# tm4c123_dev_board.net
KiCad netlist of a schematic drawn in Altium Designer
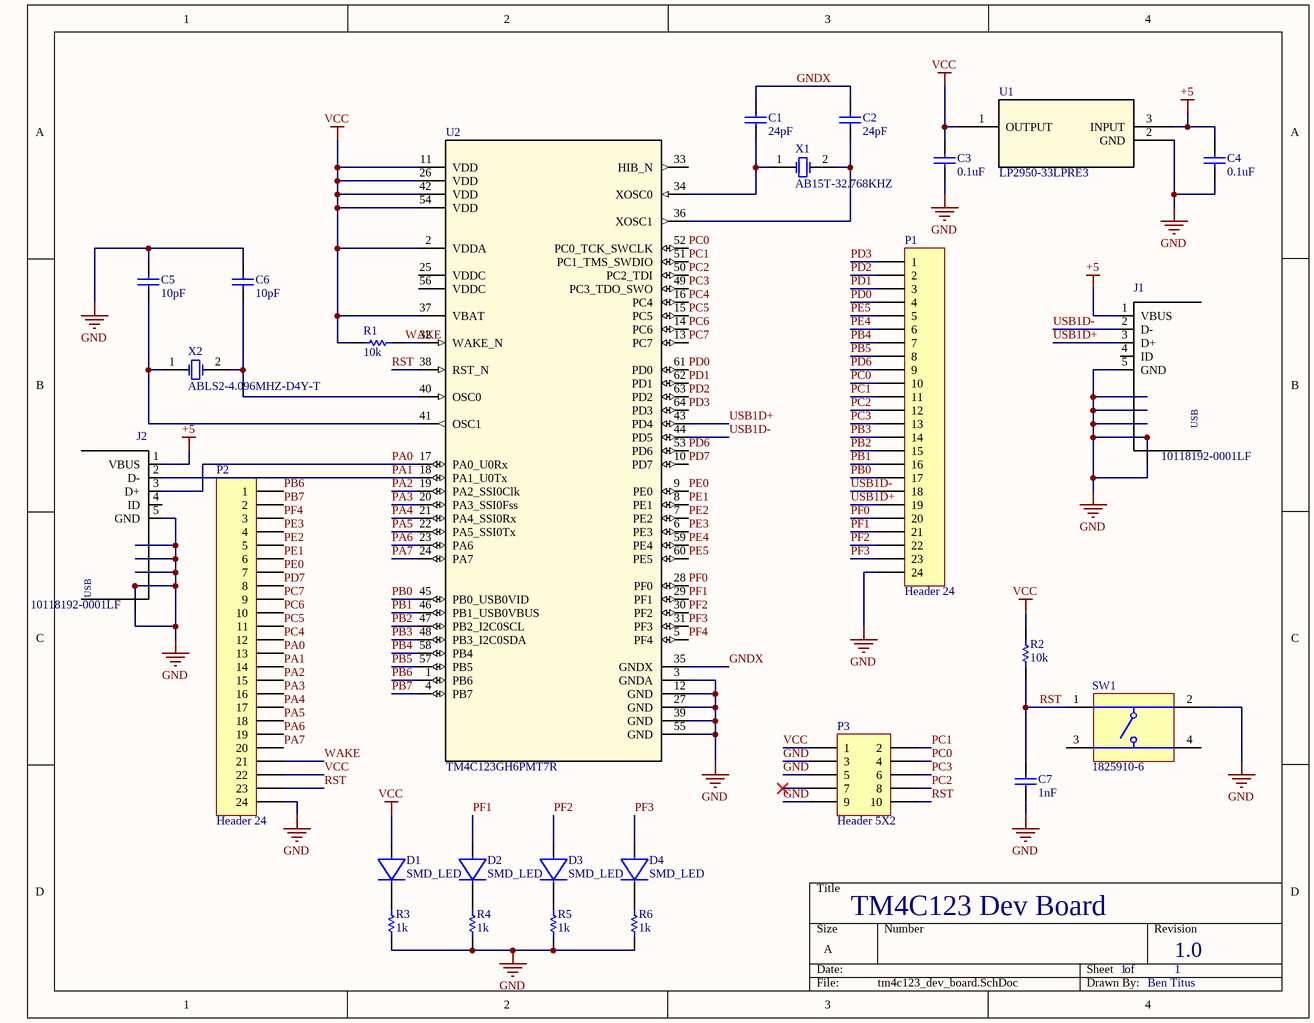
[diagram p0: tm4c123_dev_board.SchDoc]

(export (version "E")
  (design (tool "Eeschema 10.0.6"))
  (components
    (comp (ref "C1")
      (value "24pF")
      (footprint "CAPC0805(2012)145_L")
      (description "0805 (2012 Metric) Chip Capacitor")
      (libsource (lib "Altium Content Vault") (part "CAP_5"))
    )
    (comp (ref "C2")
      (value "24pF")
      (footprint "CAPC0805(2012)145_L")
      (description "0805 (2012 Metric) Chip Capacitor")
      (libsource (lib "Altium Content Vault") (part "CAP_5"))
    )
    (comp (ref "C3")
      (value "0.1uF")
      (footprint "CAPC0805(2012)145_L")
      (description "0805 (2012 Metric) Chip Capacitor")
      (libsource (lib "Altium Content Vault") (part "CAP_5"))
    )
    (comp (ref "C4")
      (value "0.1uF")
      (footprint "CAPC0805(2012)145_L")
      (description "0805 (2012 Metric) Chip Capacitor")
      (libsource (lib "Altium Content Vault") (part "CAP_5"))
    )
    (comp (ref "C5")
      (value "10pF")
      (footprint "CAPC0805(2012)145_L")
      (description "0805 (2012 Metric) Chip Capacitor")
      (libsource (lib "Altium Content Vault") (part "CAP_5"))
    )
    (comp (ref "C6")
      (value "10pF")
      (footprint "CAPC0805(2012)145_L")
      (description "0805 (2012 Metric) Chip Capacitor")
      (libsource (lib "Altium Content Vault") (part "CAP_5"))
    )
    (comp (ref "C7")
      (value "1nF")
      (footprint "CAPC0805(2012)145_L")
      (description "0805 (2012 Metric) Chip Capacitor")
      (libsource (lib "Altium Content Vault") (part "CAP_5"))
    )
    (comp (ref "D1")
      (value "SMD_LED")
      (footprint "0805 Diode")
      (libsource (lib "Custom_Lib") (part "SMD_LED"))
    )
    (comp (ref "D2")
      (value "SMD_LED")
      (footprint "0805 Diode")
      (libsource (lib "Custom_Lib") (part "SMD_LED"))
    )
    (comp (ref "D3")
      (value "SMD_LED")
      (footprint "0805 Diode")
      (libsource (lib "Custom_Lib") (part "SMD_LED"))
    )
    (comp (ref "D4")
      (value "SMD_LED")
      (footprint "0805 Diode")
      (libsource (lib "Custom_Lib") (part "SMD_LED"))
    )
    (comp (ref "J1")
      (value "10118192-0001LF")
      (footprint "10118192-0001LF_10118192-0001LF(Primary)")
      (description "CONN USB MICRO B RECPT SMT R/A")
      (fields (field (name "MF") "Amphenol"))
      (libsource (lib "Custom_Lib") (part "10118192-0001LF"))
    )
    (comp (ref "J2")
      (value "10118192-0001LF")
      (footprint "10118192-0001LF_10118192-0001LF(Primary)")
      (description "CONN USB MICRO B RECPT SMT R/A")
      (fields (field (name "MF") "Amphenol"))
      (libsource (lib "Custom_Lib") (part "10118192-0001LF"))
    )
    (comp (ref "P1")
      (value "Header 24")
      (footprint "HDR1X24")
      (description "Header, 24-Pin")
      (fields (field (name "PUBLISHER") "Altium Limited"))
      (libsource (lib "Miscellaneous Connectors") (part "Header 24"))
    )
    (comp (ref "P2")
      (value "Header 24")
      (footprint "HDR1X24")
      (description "Header, 24-Pin")
      (fields (field (name "PUBLISHER") "Altium Limited"))
      (libsource (lib "") (part "Header 24_1"))
    )
    (comp (ref "P3")
      (value "Header 5X2")
      (footprint "HDR2X5")
      (description "Header, 5-Pin, Dual row")
      (fields (field (name "PUBLISHER") "Altium Limited"))
      (libsource (lib "Miscellaneous Connectors") (part "Header 5X2"))
    )
    (comp (ref "R1")
      (value "10k")
      (footprint "RESC0805(2012)_L")
      (description "0805 (2012 Metric) Chip Resistor")
      (libsource (lib "Altium Content Vault") (part "RES_3"))
    )
    (comp (ref "R2")
      (value "10k")
      (footprint "RESC0805(2012)_L")
      (description "0805 (2012 Metric) Chip Resistor")
      (libsource (lib "Altium Content Vault") (part "RES_3"))
    )
    (comp (ref "R3")
      (value "1k")
      (footprint "RESC0805(2012)_L")
      (description "0805 (2012 Metric) Chip Resistor")
      (libsource (lib "Altium Content Vault") (part "RES_3"))
    )
    (comp (ref "R4")
      (value "1k")
      (footprint "RESC0805(2012)_L")
      (description "0805 (2012 Metric) Chip Resistor")
      (libsource (lib "Altium Content Vault") (part "RES_3"))
    )
    (comp (ref "R5")
      (value "1k")
      (footprint "RESC0805(2012)_L")
      (description "0805 (2012 Metric) Chip Resistor")
      (libsource (lib "Altium Content Vault") (part "RES_3"))
    )
    (comp (ref "R6")
      (value "1k")
      (footprint "RESC0805(2012)_L")
      (description "0805 (2012 Metric) Chip Resistor")
      (libsource (lib "Altium Content Vault") (part "RES_3"))
    )
    (comp (ref "SW1")
      (value "1825910-6")
      (footprint "TECO-1825910-6_V")
      (description "Tact Switch, SPST-NO, 0.05 A, -35 to 85 degC, 4-Pin THD, RoHS, Bulk")
      (fields (field (name "MANUFACTURER") "TE Connectivity"))
      (libsource (lib "Altium Content Vault") (part "SW-SPST-4_A"))
    )
    (comp (ref "U1")
      (value "LP2950-33LPRE3")
      (footprint "LP3")
      (description "Imported")
      (fields (field (name "MANUFACTURER") "Texas Instruments"))
      (libsource (lib "lp2950-33") (part "LP2950-33LPRE3"))
    )
    (comp (ref "U2")
      (value "TM4C123GH6PMT7R")
      (footprint "PM0064A_N")
      (description "Imported")
      (fields
        (field (name "PARTNUMBER") "TM4C123GH6PMTR")
        (field (name "ALTERNATE_PARTNUMBER") "TM4C123GH6PMT")
      )
      (libsource (lib "Custom_Lib") (part "TM4C123GH6PMT7R"))
    )
    (comp (ref "X1")
      (value "AB15T-32.768KHZ")
      (footprint "ABRA-AB15T-2_V")
      (fields (field (name "MANUFACTURER") "Abracon"))
      (libsource (lib "Altium Content Vault") (part "ABRA-XTAL_1-2-2"))
    )
    (comp (ref "X2")
      (value "ABLS2-4.096MHZ-D4Y-T")
      (footprint "ABRA-ABLS2-2_V")
      (fields (field (name "MANUFACTURER") "Abracon"))
      (libsource (lib "Altium Content Vault") (part "ABRA-XTAL_1-2-2"))
    )
  )
  (nets
    (net (code "1") (name "+5") (class "Default")
      (node (ref "C4") (pin "2") (pinfunction "2_2") (pintype "passive"))
      (node (ref "J1") (pin "1") (pinfunction "VBUS_1") (pintype "passive"))
      (node (ref "J2") (pin "1") (pinfunction "VBUS_1") (pintype "passive"))
      (node (ref "U1") (pin "3") (pinfunction "INPUT_3") (pintype "power_in"))
    )
    (net (code "2") (name "/GNDX") (class "Default")
      (node (ref "C1") (pin "2") (pinfunction "2_2") (pintype "passive"))
      (node (ref "C2") (pin "2") (pinfunction "2_2") (pintype "passive"))
      (node (ref "U2") (pin "35") (pinfunction "GNDX_35") (pintype "power_in"))
    )
    (net (code "3") (name "/PA0") (class "Default")
      (node (ref "J2") (pin "3") (pinfunction "D+_3") (pintype "passive"))
      (node (ref "P2") (pin "13") (pinfunction "13_13") (pintype "passive"))
      (node (ref "U2") (pin "17") (pinfunction "PA0_U0Rx_17") (pintype "bidirectional"))
    )
    (net (code "4") (name "/PA1") (class "Default")
      (node (ref "J2") (pin "2") (pinfunction "D-_2") (pintype "passive"))
      (node (ref "P2") (pin "14") (pinfunction "14_14") (pintype "passive"))
      (node (ref "U2") (pin "18") (pinfunction "PA1_U0Tx_18") (pintype "bidirectional"))
    )
    (net (code "5") (name "/PA2") (class "Default")
      (node (ref "P2") (pin "15") (pinfunction "15_15") (pintype "passive"))
      (node (ref "U2") (pin "19") (pinfunction "PA2_SSI0Clk_19") (pintype "bidirectional"))
    )
    (net (code "6") (name "/PA3") (class "Default")
      (node (ref "P2") (pin "16") (pinfunction "16_16") (pintype "passive"))
      (node (ref "U2") (pin "20") (pinfunction "PA3_SSI0Fss_20") (pintype "bidirectional"))
    )
    (net (code "7") (name "/PA4") (class "Default")
      (node (ref "P2") (pin "17") (pinfunction "17_17") (pintype "passive"))
      (node (ref "U2") (pin "21") (pinfunction "PA4_SSI0Rx_21") (pintype "bidirectional"))
    )
    (net (code "8") (name "/PA5") (class "Default")
      (node (ref "P2") (pin "18") (pinfunction "18_18") (pintype "passive"))
      (node (ref "U2") (pin "22") (pinfunction "PA5_SSI0Tx_22") (pintype "bidirectional"))
    )
    (net (code "9") (name "/PA6") (class "Default")
      (node (ref "P2") (pin "19") (pinfunction "19_19") (pintype "passive"))
      (node (ref "U2") (pin "23") (pinfunction "PA6_23") (pintype "bidirectional"))
    )
    (net (code "10") (name "/PA7") (class "Default")
      (node (ref "P2") (pin "20") (pinfunction "20_20") (pintype "passive"))
      (node (ref "U2") (pin "24") (pinfunction "PA7_24") (pintype "bidirectional"))
    )
    (net (code "11") (name "/PB0") (class "Default")
      (node (ref "P1") (pin "17") (pinfunction "17_17") (pintype "passive"))
      (node (ref "U2") (pin "45") (pinfunction "PB0_USB0VID_45") (pintype "bidirectional"))
    )
    (net (code "12") (name "/PB1") (class "Default")
      (node (ref "P1") (pin "16") (pinfunction "16_16") (pintype "passive"))
      (node (ref "U2") (pin "46") (pinfunction "PB1_USB0VBUS_46") (pintype "bidirectional"))
    )
    (net (code "13") (name "/PB2") (class "Default")
      (node (ref "P1") (pin "15") (pinfunction "15_15") (pintype "passive"))
      (node (ref "U2") (pin "47") (pinfunction "PB2_I2C0SCL_47") (pintype "bidirectional"))
    )
    (net (code "14") (name "/PB3") (class "Default")
      (node (ref "P1") (pin "14") (pinfunction "14_14") (pintype "passive"))
      (node (ref "U2") (pin "48") (pinfunction "PB3_I2C0SDA_48") (pintype "bidirectional"))
    )
    (net (code "15") (name "/PB4") (class "Default")
      (node (ref "P1") (pin "7") (pinfunction "7_7") (pintype "passive"))
      (node (ref "U2") (pin "58") (pinfunction "PB4_58") (pintype "bidirectional"))
    )
    (net (code "16") (name "/PB5") (class "Default")
      (node (ref "P1") (pin "8") (pinfunction "8_8") (pintype "passive"))
      (node (ref "U2") (pin "57") (pinfunction "PB5_57") (pintype "bidirectional"))
    )
    (net (code "17") (name "/PB6") (class "Default")
      (node (ref "P2") (pin "1") (pinfunction "1_1") (pintype "passive"))
      (node (ref "U2") (pin "1") (pinfunction "PB6_1") (pintype "bidirectional"))
    )
    (net (code "18") (name "/PB7") (class "Default")
      (node (ref "P2") (pin "2") (pinfunction "2_2") (pintype "passive"))
      (node (ref "U2") (pin "4") (pinfunction "PB7_4") (pintype "bidirectional"))
    )
    (net (code "19") (name "/PC0") (class "Default")
      (node (ref "P1") (pin "10") (pinfunction "10_10") (pintype "passive"))
      (node (ref "P3") (pin "4") (pinfunction "4_4") (pintype "passive"))
      (node (ref "U2") (pin "52") (pinfunction "PC0_TCK_SWCLK_52") (pintype "bidirectional"))
    )
    (net (code "20") (name "/PC1") (class "Default")
      (node (ref "P1") (pin "11") (pinfunction "11_11") (pintype "passive"))
      (node (ref "P3") (pin "2") (pinfunction "2_2") (pintype "passive"))
      (node (ref "U2") (pin "51") (pinfunction "PC1_TMS_SWDIO_51") (pintype "bidirectional"))
    )
    (net (code "21") (name "/PC2") (class "Default")
      (node (ref "P1") (pin "12") (pinfunction "12_12") (pintype "passive"))
      (node (ref "P3") (pin "8") (pinfunction "8_8") (pintype "passive"))
      (node (ref "U2") (pin "50") (pinfunction "PC2_TDI_50") (pintype "bidirectional"))
    )
    (net (code "22") (name "/PC3") (class "Default")
      (node (ref "P1") (pin "13") (pinfunction "13_13") (pintype "passive"))
      (node (ref "P3") (pin "6") (pinfunction "6_6") (pintype "passive"))
      (node (ref "U2") (pin "49") (pinfunction "PC3_TDO_SWO_49") (pintype "bidirectional"))
    )
    (net (code "23") (name "/PC4") (class "Default")
      (node (ref "P2") (pin "12") (pinfunction "12_12") (pintype "passive"))
      (node (ref "U2") (pin "16") (pinfunction "PC4_16") (pintype "bidirectional"))
    )
    (net (code "24") (name "/PC5") (class "Default")
      (node (ref "P2") (pin "11") (pinfunction "11_11") (pintype "passive"))
      (node (ref "U2") (pin "15") (pinfunction "PC5_15") (pintype "bidirectional"))
    )
    (net (code "25") (name "/PC6") (class "Default")
      (node (ref "P2") (pin "10") (pinfunction "10_10") (pintype "passive"))
      (node (ref "U2") (pin "14") (pinfunction "PC6_14") (pintype "bidirectional"))
    )
    (net (code "26") (name "/PC7") (class "Default")
      (node (ref "P2") (pin "9") (pinfunction "9_9") (pintype "passive"))
      (node (ref "U2") (pin "13") (pinfunction "PC7_13") (pintype "bidirectional"))
    )
    (net (code "27") (name "/PD0") (class "Default")
      (node (ref "P1") (pin "4") (pinfunction "4_4") (pintype "passive"))
      (node (ref "U2") (pin "61") (pinfunction "PD0_61") (pintype "bidirectional"))
    )
    (net (code "28") (name "/PD1") (class "Default")
      (node (ref "P1") (pin "3") (pinfunction "3_3") (pintype "passive"))
      (node (ref "U2") (pin "62") (pinfunction "PD1_62") (pintype "bidirectional"))
    )
    (net (code "29") (name "/PD2") (class "Default")
      (node (ref "P1") (pin "2") (pinfunction "2_2") (pintype "passive"))
      (node (ref "U2") (pin "63") (pinfunction "PD2_63") (pintype "bidirectional"))
    )
    (net (code "30") (name "/PD3") (class "Default")
      (node (ref "P1") (pin "1") (pinfunction "1_1") (pintype "passive"))
      (node (ref "U2") (pin "64") (pinfunction "PD3_64") (pintype "bidirectional"))
    )
    (net (code "31") (name "/PD6") (class "Default")
      (node (ref "P1") (pin "9") (pinfunction "9_9") (pintype "passive"))
      (node (ref "U2") (pin "53") (pinfunction "PD6_53") (pintype "bidirectional"))
    )
    (net (code "32") (name "/PD7") (class "Default")
      (node (ref "P2") (pin "8") (pinfunction "8_8") (pintype "passive"))
      (node (ref "U2") (pin "10") (pinfunction "PD7_10") (pintype "bidirectional"))
    )
    (net (code "33") (name "/PE0") (class "Default")
      (node (ref "P2") (pin "7") (pinfunction "7_7") (pintype "passive"))
      (node (ref "U2") (pin "9") (pinfunction "PE0_9") (pintype "bidirectional"))
    )
    (net (code "34") (name "/PE1") (class "Default")
      (node (ref "P2") (pin "6") (pinfunction "6_6") (pintype "passive"))
      (node (ref "U2") (pin "8") (pinfunction "PE1_8") (pintype "bidirectional"))
    )
    (net (code "35") (name "/PE2") (class "Default")
      (node (ref "P2") (pin "5") (pinfunction "5_5") (pintype "passive"))
      (node (ref "U2") (pin "7") (pinfunction "PE2_7") (pintype "bidirectional"))
    )
    (net (code "36") (name "/PE3") (class "Default")
      (node (ref "P2") (pin "4") (pinfunction "4_4") (pintype "passive"))
      (node (ref "U2") (pin "6") (pinfunction "PE3_6") (pintype "bidirectional"))
    )
    (net (code "37") (name "/PE4") (class "Default")
      (node (ref "P1") (pin "6") (pinfunction "6_6") (pintype "passive"))
      (node (ref "U2") (pin "59") (pinfunction "PE4_59") (pintype "bidirectional"))
    )
    (net (code "38") (name "/PE5") (class "Default")
      (node (ref "P1") (pin "5") (pinfunction "5_5") (pintype "passive"))
      (node (ref "U2") (pin "60") (pinfunction "PE5_60") (pintype "bidirectional"))
    )
    (net (code "39") (name "/PF0") (class "Default")
      (node (ref "P1") (pin "20") (pinfunction "20_20") (pintype "passive"))
      (node (ref "U2") (pin "28") (pinfunction "PF0_28") (pintype "bidirectional"))
    )
    (net (code "40") (name "/PF1") (class "Default")
      (node (ref "D2") (pin "1") (pintype "passive"))
      (node (ref "P1") (pin "21") (pinfunction "21_21") (pintype "passive"))
      (node (ref "U2") (pin "29") (pinfunction "PF1_29") (pintype "bidirectional"))
    )
    (net (code "41") (name "/PF2") (class "Default")
      (node (ref "D3") (pin "1") (pintype "passive"))
      (node (ref "P1") (pin "22") (pinfunction "22_22") (pintype "passive"))
      (node (ref "U2") (pin "30") (pinfunction "PF2_30") (pintype "bidirectional"))
    )
    (net (code "42") (name "/PF3") (class "Default")
      (node (ref "D4") (pin "1") (pintype "passive"))
      (node (ref "P1") (pin "23") (pinfunction "23_23") (pintype "passive"))
      (node (ref "U2") (pin "31") (pinfunction "PF3_31") (pintype "bidirectional"))
    )
    (net (code "43") (name "/PF4") (class "Default")
      (node (ref "P2") (pin "3") (pinfunction "3_3") (pintype "passive"))
      (node (ref "U2") (pin "5") (pinfunction "PF4_5") (pintype "bidirectional"))
    )
    (net (code "44") (name "/RST") (class "Default")
      (node (ref "C7") (pin "2") (pinfunction "2_2") (pintype "passive"))
      (node (ref "P2") (pin "23") (pinfunction "23_23") (pintype "passive"))
      (node (ref "P3") (pin "10") (pinfunction "10_10") (pintype "passive"))
      (node (ref "R2") (pin "1") (pinfunction "1_1") (pintype "passive"))
      (node (ref "SW1") (pin "1") (pinfunction "1_1") (pintype "passive"))
      (node (ref "U2") (pin "38") (pinfunction "RST_N_38") (pintype "input"))
    )
    (net (code "45") (name "/USB1D+") (class "Default")
      (node (ref "J1") (pin "3") (pinfunction "D+_3") (pintype "passive"))
      (node (ref "P1") (pin "19") (pinfunction "19_19") (pintype "passive"))
      (node (ref "U2") (pin "43") (pinfunction "PD4_43") (pintype "bidirectional"))
    )
    (net (code "46") (name "/USB1D-") (class "Default")
      (node (ref "J1") (pin "2") (pinfunction "D-_2") (pintype "passive"))
      (node (ref "P1") (pin "18") (pinfunction "18_18") (pintype "passive"))
      (node (ref "U2") (pin "44") (pinfunction "PD5_44") (pintype "bidirectional"))
    )
    (net (code "47") (name "/WAKE") (class "Default")
      (node (ref "P2") (pin "21") (pinfunction "21_21") (pintype "passive"))
      (node (ref "R1") (pin "2") (pinfunction "2_2") (pintype "passive"))
      (node (ref "U2") (pin "32") (pinfunction "WAKE_N_32") (pintype "input"))
    )
    (net (code "48") (name "GND") (class "Default")
      (node (ref "C3") (pin "1") (pinfunction "1_1") (pintype "passive"))
      (node (ref "C4") (pin "1") (pinfunction "1_1") (pintype "passive"))
      (node (ref "C5") (pin "2") (pinfunction "2_2") (pintype "passive"))
      (node (ref "C6") (pin "2") (pinfunction "2_2") (pintype "passive"))
      (node (ref "C7") (pin "1") (pinfunction "1_1") (pintype "passive"))
      (node (ref "J1") (pin "5") (pinfunction "GND_5") (pintype "passive"))
      (node (ref "J1") (pin "M1") (pinfunction "S_M1") (pintype "passive"))
      (node (ref "J1") (pin "M2") (pinfunction "S_M2") (pintype "passive"))
      (node (ref "J1") (pin "S1") (pinfunction "S_S1") (pintype "passive"))
      (node (ref "J1") (pin "S2") (pinfunction "S_S2") (pintype "passive"))
      (node (ref "J1") (pin "S3") (pinfunction "S_S3") (pintype "passive"))
      (node (ref "J1") (pin "S4") (pinfunction "S_S4") (pintype "passive"))
      (node (ref "J2") (pin "5") (pinfunction "GND_5") (pintype "passive"))
      (node (ref "J2") (pin "M1") (pinfunction "S_M1") (pintype "passive"))
      (node (ref "J2") (pin "M2") (pinfunction "S_M2") (pintype "passive"))
      (node (ref "J2") (pin "S1") (pinfunction "S_S1") (pintype "passive"))
      (node (ref "J2") (pin "S2") (pinfunction "S_S2") (pintype "passive"))
      (node (ref "J2") (pin "S3") (pinfunction "S_S3") (pintype "passive"))
      (node (ref "J2") (pin "S4") (pinfunction "S_S4") (pintype "passive"))
      (node (ref "P1") (pin "24") (pinfunction "24_24") (pintype "passive"))
      (node (ref "P2") (pin "24") (pinfunction "24_24") (pintype "passive"))
      (node (ref "P3") (pin "3") (pinfunction "3_3") (pintype "passive"))
      (node (ref "P3") (pin "5") (pinfunction "5_5") (pintype "passive"))
      (node (ref "P3") (pin "9") (pinfunction "9_9") (pintype "passive"))
      (node (ref "R3") (pin "1") (pinfunction "1_1") (pintype "passive"))
      (node (ref "R4") (pin "1") (pinfunction "1_1") (pintype "passive"))
      (node (ref "R5") (pin "1") (pinfunction "1_1") (pintype "passive"))
      (node (ref "R6") (pin "1") (pinfunction "1_1") (pintype "passive"))
      (node (ref "SW1") (pin "2") (pinfunction "2_2") (pintype "passive"))
      (node (ref "U1") (pin "2") (pinfunction "GND_2") (pintype "power_in"))
      (node (ref "U2") (pin "12") (pinfunction "GND_12") (pintype "power_in"))
      (node (ref "U2") (pin "27") (pinfunction "GND_27") (pintype "power_in"))
      (node (ref "U2") (pin "3") (pinfunction "GNDA_3") (pintype "power_in"))
      (node (ref "U2") (pin "39") (pinfunction "GND_39") (pintype "power_in"))
      (node (ref "U2") (pin "55") (pinfunction "GND_55") (pintype "power_in"))
    )
    (net (code "49") (name "Net-(D1-Pad2)") (class "Default")
      (node (ref "D1") (pin "2") (pintype "passive"))
      (node (ref "R3") (pin "2") (pinfunction "2_2") (pintype "passive"))
    )
    (net (code "50") (name "Net-(D2-Pad2)") (class "Default")
      (node (ref "D2") (pin "2") (pintype "passive"))
      (node (ref "R4") (pin "2") (pinfunction "2_2") (pintype "passive"))
    )
    (net (code "51") (name "Net-(D3-Pad2)") (class "Default")
      (node (ref "D3") (pin "2") (pintype "passive"))
      (node (ref "R5") (pin "2") (pinfunction "2_2") (pintype "passive"))
    )
    (net (code "52") (name "Net-(D4-Pad2)") (class "Default")
      (node (ref "D4") (pin "2") (pintype "passive"))
      (node (ref "R6") (pin "2") (pinfunction "2_2") (pintype "passive"))
    )
    (net (code "53") (name "Net-(U2-OSC0)") (class "Default")
      (node (ref "C6") (pin "1") (pinfunction "1_1") (pintype "passive"))
      (node (ref "U2") (pin "40") (pinfunction "OSC0_40") (pintype "input"))
      (node (ref "X2") (pin "2") (pinfunction "X2_2") (pintype "passive"))
    )
    (net (code "54") (name "Net-(U2-OSC1)") (class "Default")
      (node (ref "C5") (pin "1") (pinfunction "1_1") (pintype "passive"))
      (node (ref "U2") (pin "41") (pinfunction "OSC1_41") (pintype "output"))
      (node (ref "X2") (pin "1") (pinfunction "X1_1") (pintype "passive"))
    )
    (net (code "55") (name "Net-(U2-XOSC0)") (class "Default")
      (node (ref "C1") (pin "1") (pinfunction "1_1") (pintype "passive"))
      (node (ref "U2") (pin "34") (pinfunction "XOSC0_34") (pintype "input"))
      (node (ref "X1") (pin "1") (pinfunction "X1_1") (pintype "passive"))
    )
    (net (code "56") (name "Net-(U2-XOSC1)") (class "Default")
      (node (ref "C2") (pin "1") (pinfunction "1_1") (pintype "passive"))
      (node (ref "U2") (pin "36") (pinfunction "XOSC1_36") (pintype "output"))
      (node (ref "X1") (pin "2") (pinfunction "X2_2") (pintype "passive"))
    )
    (net (code "57") (name "VCC") (class "Default")
      (node (ref "C3") (pin "2") (pinfunction "2_2") (pintype "passive"))
      (node (ref "D1") (pin "1") (pintype "passive"))
      (node (ref "P2") (pin "22") (pinfunction "22_22") (pintype "passive"))
      (node (ref "P3") (pin "1") (pinfunction "1_1") (pintype "passive"))
      (node (ref "R1") (pin "1") (pinfunction "1_1") (pintype "passive"))
      (node (ref "R2") (pin "2") (pinfunction "2_2") (pintype "passive"))
      (node (ref "U1") (pin "1") (pinfunction "OUTPUT_1") (pintype "power_in"))
      (node (ref "U2") (pin "11") (pinfunction "VDD_11") (pintype "power_in"))
      (node (ref "U2") (pin "2") (pinfunction "VDDA_2") (pintype "power_in"))
      (node (ref "U2") (pin "26") (pinfunction "VDD_26") (pintype "power_in"))
      (node (ref "U2") (pin "37") (pinfunction "VBAT_37") (pintype "power_in"))
      (node (ref "U2") (pin "42") (pinfunction "VDD_42") (pintype "power_in"))
      (node (ref "U2") (pin "54") (pinfunction "VDD_54") (pintype "power_in"))
    )
    (net (code "58") (name "unconnected-(J1-ID-Pad4)") (class "Default")
      (node (ref "J1") (pin "4") (pinfunction "ID_4") (pintype "passive"))
    )
    (net (code "59") (name "unconnected-(J2-ID-Pad4)") (class "Default")
      (node (ref "J2") (pin "4") (pinfunction "ID_4") (pintype "passive"))
    )
    (net (code "60") (name "unconnected-(P3-Pad7)") (class "Default")
      (node (ref "P3") (pin "7") (pinfunction "7_7") (pintype "passive+no_connect"))
    )
    (net (code "61") (name "unconnected-(SW1-Pad3)") (class "Default")
      (node (ref "SW1") (pin "3") (pinfunction "3_3") (pintype "passive"))
    )
    (net (code "62") (name "unconnected-(SW1-Pad4)") (class "Default")
      (node (ref "SW1") (pin "4") (pinfunction "4_4") (pintype "passive"))
    )
    (net (code "63") (name "unconnected-(U2-HIB_N-Pad33)") (class "Default")
      (node (ref "U2") (pin "33") (pinfunction "HIB_N_33") (pintype "output"))
    )
    (net (code "64") (name "unconnected-(U2-VDDC-Pad25)") (class "Default")
      (node (ref "U2") (pin "25") (pinfunction "VDDC_25") (pintype "power_in"))
    )
    (net (code "65") (name "unconnected-(U2-VDDC-Pad56)") (class "Default")
      (node (ref "U2") (pin "56") (pinfunction "VDDC_56") (pintype "power_in"))
    )
  )
)
